# FootKeyboardTrial_18F14K50.net
KiCad netlist of a schematic drawn in EAGLE
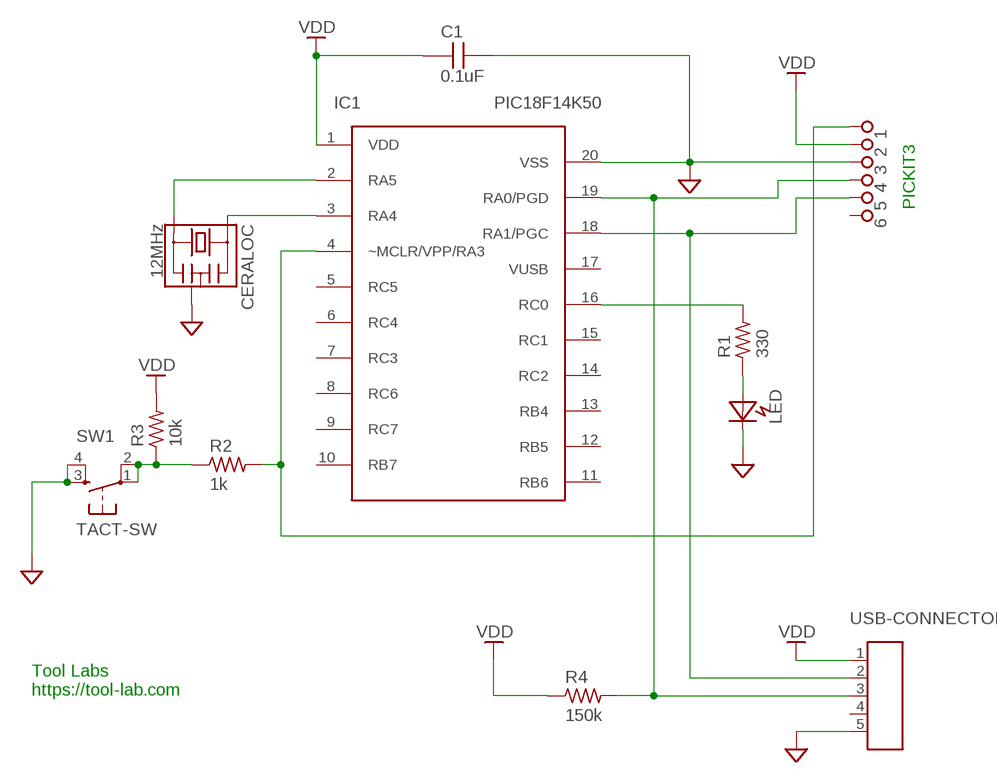
[diagram p0: schematic, sheet 1]

(export (version "E")
  (design (tool "Eeschema 10.0.6"))
  (components
    (comp (ref "1")
      (value "TP1")
      (footprint "eagle-import:TP1")
      (libsource (lib "eagle-import") (part "TP1"))
    )
    (comp (ref "2")
      (value "TP1")
      (footprint "eagle-import:TP1")
      (libsource (lib "eagle-import") (part "TP1"))
    )
    (comp (ref "3")
      (value "TP1")
      (footprint "eagle-import:TP1")
      (libsource (lib "eagle-import") (part "TP1"))
    )
    (comp (ref "4")
      (value "TP1")
      (footprint "eagle-import:TP1")
      (libsource (lib "eagle-import") (part "TP1"))
    )
    (comp (ref "5")
      (value "TP1")
      (footprint "eagle-import:TP1")
      (libsource (lib "eagle-import") (part "TP1"))
    )
    (comp (ref "6")
      (value "TP1")
      (footprint "eagle-import:TP1")
      (libsource (lib "eagle-import") (part "TP1"))
    )
    (comp (ref "C1")
      (value "0.1uF")
      (footprint "eagle-import:CAP_10X4")
      (libsource (lib "eagle-import") (part "CAP10X4"))
    )
    (comp (ref "CERALOC")
      (value "12MHz")
      (footprint "eagle-import:CSTLS")
      (libsource (lib "eagle-import") (part "CERALOCK"))
    )
    (comp (ref "IC1")
      (value "PIC18F14K50")
      (footprint "eagle-import:DIL20")
      (libsource (lib "eagle-import") (part "PIC18F1XK50"))
    )
    (comp (ref "LED")
      (value "LED")
      (footprint "eagle-import:LED_3MM_VIRT_2")
      (libsource (lib "eagle-import") (part "LED"))
    )
    (comp (ref "R1")
      (value "330")
      (footprint "eagle-import:R_0.5W_5")
      (libsource (lib "eagle-import") (part "R0.5W_5P"))
    )
    (comp (ref "R2")
      (value "1k")
      (footprint "eagle-import:R_0.5W_5")
      (libsource (lib "eagle-import") (part "R0.5W_5P"))
    )
    (comp (ref "R3")
      (value "10k")
      (footprint "eagle-import:R_0.5W_5")
      (libsource (lib "eagle-import") (part "R0.5W_5P"))
    )
    (comp (ref "R4")
      (value "150k")
      (footprint "eagle-import:R_0.5W_5")
      (libsource (lib "eagle-import") (part "R0.5W_5P"))
    )
    (comp (ref "SW1")
      (value "TACT-SW")
      (footprint "eagle-import:B3F-10X")
      (libsource (lib "eagle-import") (part "TACT-SW"))
    )
    (comp (ref "USB-CONNECTOR")
      (value "CON_5P")
      (footprint "eagle-import:CON_HRS_DIP_5")
      (libsource (lib "eagle-import") (part "CON_5P"))
    )
  )
  (nets
    (net (code "1") (name "GND") (class "Default")
      (node (ref "3") (pin "P$1") (pinfunction "P$1_P$1") (pintype "passive"))
      (node (ref "C1") (pin "2") (pinfunction "2_2") (pintype "passive"))
      (node (ref "CERALOC") (pin "2") (pinfunction "2_2") (pintype "power_in"))
      (node (ref "IC1") (pin "20") (pinfunction "VSS_20") (pintype "bidirectional"))
      (node (ref "LED") (pin "K") (pinfunction "K_K") (pintype "passive"))
      (node (ref "SW1") (pin "3") (pinfunction "S_3") (pintype "passive"))
      (node (ref "SW1") (pin "4") (pinfunction "S1_4") (pintype "passive"))
      (node (ref "USB-CONNECTOR") (pin "5") (pinfunction "5_5") (pintype "passive"))
    )
    (net (code "2") (name "Net-(IC1-RA0{slash}PGD)") (class "Default")
      (node (ref "4") (pin "P$1") (pinfunction "P$1_P$1") (pintype "passive"))
      (node (ref "IC1") (pin "19") (pinfunction "RA0/PGD_19") (pintype "bidirectional"))
      (node (ref "R4") (pin "2") (pinfunction "2_2") (pintype "passive"))
      (node (ref "USB-CONNECTOR") (pin "3") (pinfunction "3_3") (pintype "passive"))
    )
    (net (code "3") (name "Net-(IC1-RA1{slash}PGC)") (class "Default")
      (node (ref "5") (pin "P$1") (pinfunction "P$1_P$1") (pintype "passive"))
      (node (ref "IC1") (pin "18") (pinfunction "RA1/PGC_18") (pintype "bidirectional"))
      (node (ref "USB-CONNECTOR") (pin "2") (pinfunction "2_2") (pintype "passive"))
    )
    (net (code "4") (name "Net-(IC1-RA4)") (class "Default")
      (node (ref "CERALOC") (pin "1") (pinfunction "1_1") (pintype "passive"))
      (node (ref "IC1") (pin "3") (pinfunction "RA4_3") (pintype "bidirectional"))
    )
    (net (code "5") (name "Net-(IC1-RA5)") (class "Default")
      (node (ref "CERALOC") (pin "3") (pinfunction "3_3") (pintype "passive"))
      (node (ref "IC1") (pin "2") (pinfunction "RA5_2") (pintype "bidirectional"))
    )
    (net (code "6") (name "Net-(IC1-RC0)") (class "Default")
      (node (ref "IC1") (pin "16") (pinfunction "RC0_16") (pintype "bidirectional"))
      (node (ref "R1") (pin "2") (pinfunction "2_2") (pintype "passive"))
    )
    (net (code "7") (name "Net-(IC1-~{MCLR{slash}VPP{slash}RA3})") (class "Default")
      (node (ref "1") (pin "P$1") (pinfunction "P$1_P$1") (pintype "passive"))
      (node (ref "IC1") (pin "4") (pinfunction "~{MCLR/VPP/RA3}_4") (pintype "bidirectional"))
      (node (ref "R2") (pin "2") (pinfunction "2_2") (pintype "passive"))
    )
    (net (code "8") (name "Net-(LED-PadA)") (class "Default")
      (node (ref "LED") (pin "A") (pinfunction "A_A") (pintype "passive"))
      (node (ref "R1") (pin "1") (pinfunction "1_1") (pintype "passive"))
    )
    (net (code "9") (name "Net-(SW1-P)") (class "Default")
      (node (ref "R2") (pin "1") (pinfunction "1_1") (pintype "passive"))
      (node (ref "R3") (pin "1") (pinfunction "1_1") (pintype "passive"))
      (node (ref "SW1") (pin "1") (pinfunction "P_1") (pintype "passive"))
      (node (ref "SW1") (pin "2") (pinfunction "P1_2") (pintype "passive"))
    )
    (net (code "10") (name "VDD") (class "Default")
      (node (ref "2") (pin "P$1") (pinfunction "P$1_P$1") (pintype "passive"))
      (node (ref "C1") (pin "1") (pinfunction "1_1") (pintype "passive"))
      (node (ref "IC1") (pin "1") (pinfunction "VDD_1") (pintype "bidirectional"))
      (node (ref "R3") (pin "2") (pinfunction "2_2") (pintype "passive"))
      (node (ref "R4") (pin "1") (pinfunction "1_1") (pintype "passive"))
      (node (ref "USB-CONNECTOR") (pin "1") (pinfunction "1_1") (pintype "passive"))
    )
    (net (code "11") (name "unconnected-(6-PadP$1)") (class "Default")
      (node (ref "6") (pin "P$1") (pinfunction "P$1_P$1") (pintype "passive"))
    )
    (net (code "12") (name "unconnected-(IC1-RB4-Pad13)") (class "Default")
      (node (ref "IC1") (pin "13") (pinfunction "RB4_13") (pintype "bidirectional"))
    )
    (net (code "13") (name "unconnected-(IC1-RB5-Pad12)") (class "Default")
      (node (ref "IC1") (pin "12") (pinfunction "RB5_12") (pintype "bidirectional"))
    )
    (net (code "14") (name "unconnected-(IC1-RB6-Pad11)") (class "Default")
      (node (ref "IC1") (pin "11") (pinfunction "RB6_11") (pintype "bidirectional"))
    )
    (net (code "15") (name "unconnected-(IC1-RB7-Pad10)") (class "Default")
      (node (ref "IC1") (pin "10") (pinfunction "RB7_10") (pintype "bidirectional"))
    )
    (net (code "16") (name "unconnected-(IC1-RC1-Pad15)") (class "Default")
      (node (ref "IC1") (pin "15") (pinfunction "RC1_15") (pintype "bidirectional"))
    )
    (net (code "17") (name "unconnected-(IC1-RC2-Pad14)") (class "Default")
      (node (ref "IC1") (pin "14") (pinfunction "RC2_14") (pintype "bidirectional"))
    )
    (net (code "18") (name "unconnected-(IC1-RC3-Pad7)") (class "Default")
      (node (ref "IC1") (pin "7") (pinfunction "RC3_7") (pintype "bidirectional"))
    )
    (net (code "19") (name "unconnected-(IC1-RC4-Pad6)") (class "Default")
      (node (ref "IC1") (pin "6") (pinfunction "RC4_6") (pintype "bidirectional"))
    )
    (net (code "20") (name "unconnected-(IC1-RC5-Pad5)") (class "Default")
      (node (ref "IC1") (pin "5") (pinfunction "RC5_5") (pintype "bidirectional"))
    )
    (net (code "21") (name "unconnected-(IC1-RC6-Pad8)") (class "Default")
      (node (ref "IC1") (pin "8") (pinfunction "RC6_8") (pintype "bidirectional"))
    )
    (net (code "22") (name "unconnected-(IC1-RC7-Pad9)") (class "Default")
      (node (ref "IC1") (pin "9") (pinfunction "RC7_9") (pintype "bidirectional"))
    )
    (net (code "23") (name "unconnected-(IC1-VUSB-Pad17)") (class "Default")
      (node (ref "IC1") (pin "17") (pinfunction "VUSB_17") (pintype "bidirectional"))
    )
    (net (code "24") (name "unconnected-(USB-CONNECTOR-Pad4)") (class "Default")
      (node (ref "USB-CONNECTOR") (pin "4") (pinfunction "4_4") (pintype "passive"))
    )
  )
)
